# Sheet2.net
KiCad netlist of a schematic drawn in Altium Designer
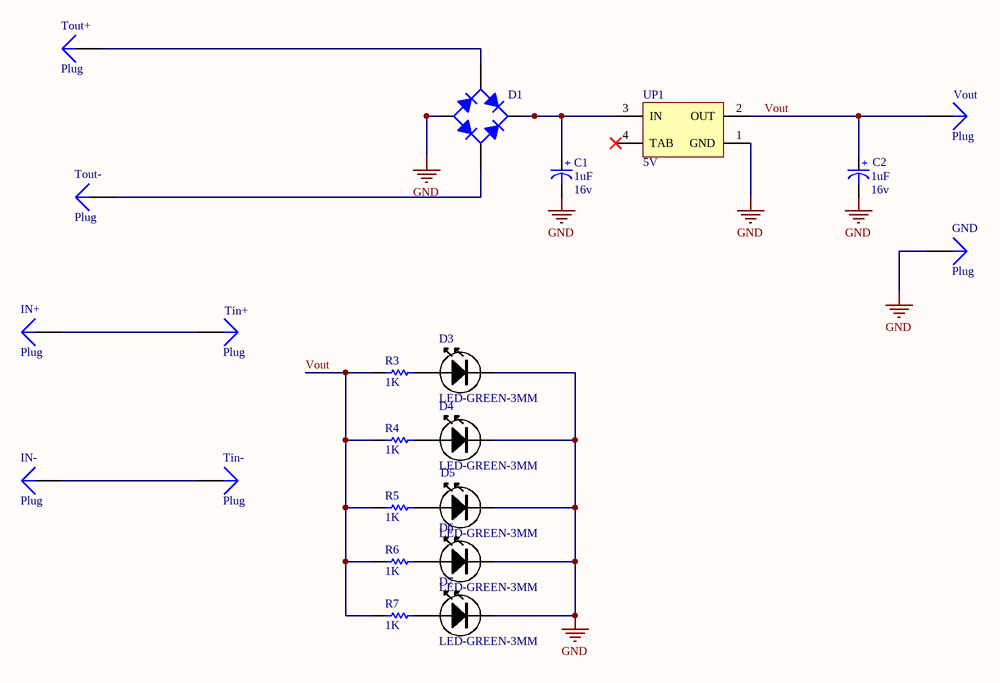
[diagram p0: Sheet2.SchDoc]

(export (version "E")
  (design (tool "Eeschema 10.0.6"))
  (components
    (comp (ref "C1")
      (value "1uF")
      (footprint "cap-ele-02.")
      (description "Capacitor_Ele")
      (fields (field (name "VOLTAGE") "16v") (field (name "PUBLISHER") "Altium Limited"))
      (libsource (lib "General_10") (part "Capacitor_Ele."))
    )
    (comp (ref "C2")
      (value "1uF")
      (footprint "cap-ele-02.")
      (description "Capacitor_Ele")
      (fields (field (name "VOLTAGE") "16v") (field (name "PUBLISHER") "Altium Limited"))
      (libsource (lib "General_10") (part "Capacitor_Ele."))
    )
    (comp (ref "D1")
      (value "Bridge SMD Package")
      (footprint "Bridge SMD Package")
      (libsource (lib "Bridge SMD Package") (part "Bridge SMD Package"))
    )
    (comp (ref "D3")
      (value "LED-GREEN-3MM")
      (footprint "LED-3MM-GREEN")
      (libsource (lib "General_05") (part "LED-GREEN-3MM"))
    )
    (comp (ref "D4")
      (value "LED-GREEN-3MM")
      (footprint "LED-3MM-GREEN")
      (libsource (lib "General_05") (part "LED-GREEN-3MM"))
    )
    (comp (ref "D5")
      (value "LED-GREEN-3MM")
      (footprint "LED-3MM-GREEN")
      (libsource (lib "General_05") (part "LED-GREEN-3MM"))
    )
    (comp (ref "D6")
      (value "LED-GREEN-3MM")
      (footprint "LED-3MM-GREEN")
      (libsource (lib "General_05") (part "LED-GREEN-3MM"))
    )
    (comp (ref "D7")
      (value "LED-GREEN-3MM")
      (footprint "LED-3MM-GREEN")
      (libsource (lib "General_05") (part "LED-GREEN-3MM"))
    )
    (comp (ref "GND")
      (value "Plug")
      (footprint "PIN1")
      (fields (field (name "PUBLISHER") "Altium Limited"))
      (libsource (lib "Miscellaneous Connectors") (part "Plug"))
    )
    (comp (ref "IN+")
      (value "Plug")
      (footprint "PIN1")
      (fields (field (name "PUBLISHER") "Altium Limited"))
      (libsource (lib "Miscellaneous Connectors") (part "Plug"))
    )
    (comp (ref "IN-")
      (value "Plug")
      (footprint "PIN1")
      (fields (field (name "PUBLISHER") "Altium Limited"))
      (libsource (lib "Miscellaneous Connectors") (part "Plug"))
    )
    (comp (ref "R3")
      (value "1K")
      (footprint "Resistor_SMD_0603")
      (description "Resistor 0.25w")
      (fields (field (name "PUBLISHER") "Altium Limited"))
      (libsource (lib "General_10") (part "Resistor"))
    )
    (comp (ref "R4")
      (value "1K")
      (footprint "Resistor_SMD_0603")
      (description "Resistor 0.25w")
      (fields (field (name "PUBLISHER") "Altium Limited"))
      (libsource (lib "General_10") (part "Resistor"))
    )
    (comp (ref "R5")
      (value "1K")
      (footprint "Resistor_SMD_0603")
      (description "Resistor 0.25w")
      (fields (field (name "PUBLISHER") "Altium Limited"))
      (libsource (lib "General_10") (part "Resistor"))
    )
    (comp (ref "R6")
      (value "1K")
      (footprint "Resistor_SMD_0603")
      (description "Resistor 0.25w")
      (fields (field (name "PUBLISHER") "Altium Limited"))
      (libsource (lib "General_10") (part "Resistor"))
    )
    (comp (ref "R7")
      (value "1K")
      (footprint "Resistor_SMD_0603")
      (description "Resistor 0.25w")
      (fields (field (name "PUBLISHER") "Altium Limited"))
      (libsource (lib "General_10") (part "Resistor"))
    )
    (comp (ref "Tin+")
      (value "Plug")
      (footprint "PIN1")
      (fields (field (name "PUBLISHER") "Altium Limited"))
      (libsource (lib "Miscellaneous Connectors") (part "Plug"))
    )
    (comp (ref "Tin-")
      (value "Plug")
      (footprint "PIN1")
      (fields (field (name "PUBLISHER") "Altium Limited"))
      (libsource (lib "Miscellaneous Connectors") (part "Plug"))
    )
    (comp (ref "Tout+")
      (value "Plug")
      (footprint "PIN1")
      (fields (field (name "PUBLISHER") "Altium Limited"))
      (libsource (lib "Miscellaneous Connectors") (part "Plug"))
    )
    (comp (ref "Tout-")
      (value "Plug")
      (footprint "PIN1")
      (fields (field (name "PUBLISHER") "Altium Limited"))
      (libsource (lib "Miscellaneous Connectors") (part "Plug"))
    )
    (comp (ref "UP1")
      (value "5V")
      (footprint "SOT223_N")
      (description "x.x Volt, 800mA Low-Dropout Linear Regulator, 4-pin SOT-223")
      (fields (field (name "DESIGNER") "Ali Hafizi"))
      (libsource (lib "General_14") (part "AMS1117-x.x"))
    )
    (comp (ref "Vout")
      (value "Plug")
      (footprint "PIN1")
      (fields (field (name "PUBLISHER") "Altium Limited"))
      (libsource (lib "Miscellaneous Connectors") (part "Plug"))
    )
  )
  (nets
    (net (code "1") (name "/Vout") (class "Default")
      (node (ref "C2") (pin "1") (pinfunction "+_1") (pintype "passive"))
      (node (ref "R3") (pin "2") (pinfunction "2_2") (pintype "passive"))
      (node (ref "R4") (pin "2") (pinfunction "2_2") (pintype "passive"))
      (node (ref "R5") (pin "2") (pinfunction "2_2") (pintype "passive"))
      (node (ref "R6") (pin "2") (pinfunction "2_2") (pintype "passive"))
      (node (ref "R7") (pin "2") (pinfunction "2_2") (pintype "passive"))
      (node (ref "UP1") (pin "2") (pinfunction "OUT_2") (pintype "power_in"))
      (node (ref "Vout") (pin "1") (pinfunction "1_1") (pintype "passive"))
    )
    (net (code "2") (name "GND") (class "Default")
      (node (ref "C1") (pin "2") (pinfunction "-_2") (pintype "passive"))
      (node (ref "C2") (pin "2") (pinfunction "-_2") (pintype "passive"))
      (node (ref "D1") (pin "4") (pinfunction "-_4") (pintype "passive"))
      (node (ref "D3") (pin "K") (pintype "passive"))
      (node (ref "D4") (pin "K") (pintype "passive"))
      (node (ref "D5") (pin "K") (pintype "passive"))
      (node (ref "D6") (pin "K") (pintype "passive"))
      (node (ref "D7") (pin "K") (pintype "passive"))
      (node (ref "GND") (pin "1") (pinfunction "1_1") (pintype "passive"))
      (node (ref "UP1") (pin "1") (pinfunction "GND_1") (pintype "power_in"))
    )
    (net (code "3") (name "Net-(C1-+)") (class "Default")
      (node (ref "C1") (pin "1") (pinfunction "+_1") (pintype "passive"))
      (node (ref "D1") (pin "1") (pinfunction "+_1") (pintype "passive"))
      (node (ref "UP1") (pin "3") (pinfunction "IN_3") (pintype "power_in"))
    )
    (net (code "4") (name "Net-(D1-AC-Pad2)") (class "Default")
      (node (ref "D1") (pin "2") (pinfunction "AC_2") (pintype "passive"))
      (node (ref "Tout+") (pin "1") (pinfunction "1_1") (pintype "passive"))
    )
    (net (code "5") (name "Net-(D1-AC-Pad3)") (class "Default")
      (node (ref "D1") (pin "3") (pinfunction "AC_3") (pintype "passive"))
      (node (ref "Tout-") (pin "1") (pinfunction "1_1") (pintype "passive"))
    )
    (net (code "6") (name "Net-(D3-PadA)") (class "Default")
      (node (ref "D3") (pin "A") (pintype "passive"))
      (node (ref "R3") (pin "1") (pinfunction "1_1") (pintype "passive"))
    )
    (net (code "7") (name "Net-(D4-PadA)") (class "Default")
      (node (ref "D4") (pin "A") (pintype "passive"))
      (node (ref "R4") (pin "1") (pinfunction "1_1") (pintype "passive"))
    )
    (net (code "8") (name "Net-(D5-PadA)") (class "Default")
      (node (ref "D5") (pin "A") (pintype "passive"))
      (node (ref "R5") (pin "1") (pinfunction "1_1") (pintype "passive"))
    )
    (net (code "9") (name "Net-(D6-PadA)") (class "Default")
      (node (ref "D6") (pin "A") (pintype "passive"))
      (node (ref "R6") (pin "1") (pinfunction "1_1") (pintype "passive"))
    )
    (net (code "10") (name "Net-(D7-PadA)") (class "Default")
      (node (ref "D7") (pin "A") (pintype "passive"))
      (node (ref "R7") (pin "1") (pinfunction "1_1") (pintype "passive"))
    )
    (net (code "11") (name "Net-(IN+-Pad1)") (class "Default")
      (node (ref "IN+") (pin "1") (pinfunction "1_1") (pintype "passive"))
      (node (ref "Tin+") (pin "1") (pinfunction "1_1") (pintype "passive"))
    )
    (net (code "12") (name "Net-(IN--Pad1)") (class "Default")
      (node (ref "IN-") (pin "1") (pinfunction "1_1") (pintype "passive"))
      (node (ref "Tin-") (pin "1") (pinfunction "1_1") (pintype "passive"))
    )
    (net (code "13") (name "unconnected-(UP1-TAB-Pad4)") (class "Default")
      (node (ref "UP1") (pin "4") (pinfunction "TAB_4") (pintype "power_in+no_connect"))
    )
  )
)
